# UART.net
KiCad netlist of a schematic drawn in Altium Designer
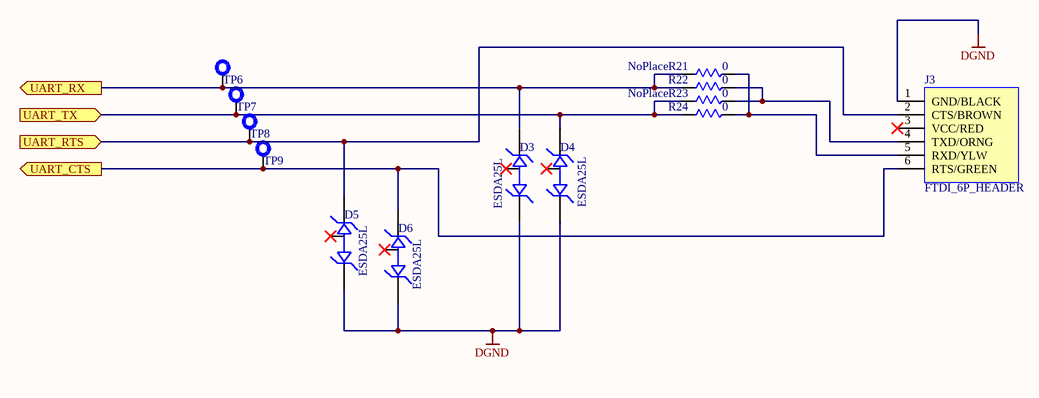
[diagram p0: UART.SchDoc]

(export (version "E")
  (design (tool "Eeschema 10.0.6"))
  (components
    (comp (ref "D3")
      (value "ESDA25L")
      (footprint "SOT23_3_HD")
      (description "TRANSIL ARRAY DUAL ESD SOT-23")
      (fields (field (name "MANUFACTURER") "STMicroelectronics"))
      (libsource (lib "ECGLib") (part "ESDA25L"))
    )
    (comp (ref "D4")
      (value "ESDA25L")
      (footprint "SOT23_3_HD")
      (description "TRANSIL ARRAY DUAL ESD SOT-23")
      (fields (field (name "MANUFACTURER") "STMicroelectronics"))
      (libsource (lib "ECGLib") (part "ESDA25L"))
    )
    (comp (ref "D5")
      (value "ESDA25L")
      (footprint "SOT23_3_HD")
      (description "TRANSIL ARRAY DUAL ESD SOT-23")
      (fields (field (name "MANUFACTURER") "STMicroelectronics"))
      (libsource (lib "ECGLib") (part "ESDA25L"))
    )
    (comp (ref "D6")
      (value "ESDA25L")
      (footprint "SOT23_3_HD")
      (description "TRANSIL ARRAY DUAL ESD SOT-23")
      (fields (field (name "MANUFACTURER") "STMicroelectronics"))
      (libsource (lib "ECGLib") (part "ESDA25L"))
    )
    (comp (ref "J3")
      (value "FTDI_6P_HEADER")
      (footprint "GEC36SBSN-M89")
      (description "6 PIN FTDI HEADER")
      (fields
        (field (name "MANUFACTURER") "Sullins Connector Solutions")
        (field (name "MANUFACTURER PART NUMBER") "GEC36SBSN-M89")
      )
      (libsource (lib "ECGLib") (part "FTDI_6P_HEADER"))
    )
    (comp (ref "R21")
      (value "0")
      (footprint "RES_0603")
      (description "RES 0.0 OHM 0.1W JUMPER 0603 SMD")
      (fields
        (field (name "MANUFACTURER") "Bourns Inc")
        (field (name "MANUFACTURER PART NUMBER") "CR0603-J/-000ELF")
        (field (name "NOPLACE?") "NoPlace")
      )
      (libsource (lib "ECGLib") (part "RES_GEN"))
    )
    (comp (ref "R22")
      (value "0")
      (footprint "RES_0603")
      (description "RES 0.0 OHM 0.1W JUMPER 0603 SMD")
      (fields
        (field (name "MANUFACTURER") "Bourns Inc")
        (field (name "MANUFACTURER PART NUMBER") "CR0603-J/-000ELF")
      )
      (libsource (lib "ECGLib") (part "RES_GEN"))
    )
    (comp (ref "R23")
      (value "0")
      (footprint "RES_0603")
      (description "RES 0.0 OHM 0.1W JUMPER 0603 SMD")
      (fields
        (field (name "MANUFACTURER") "Bourns Inc")
        (field (name "MANUFACTURER PART NUMBER") "CR0603-J/-000ELF")
        (field (name "NOPLACE?") "NoPlace")
      )
      (libsource (lib "ECGLib") (part "RES_GEN"))
    )
    (comp (ref "R24")
      (value "0")
      (footprint "RES_0603")
      (description "RES 0.0 OHM 0.1W JUMPER 0603 SMD")
      (fields
        (field (name "MANUFACTURER") "Bourns Inc")
        (field (name "MANUFACTURER PART NUMBER") "CR0603-J/-000ELF")
      )
      (libsource (lib "ECGLib") (part "RES_GEN"))
    )
    (comp (ref "TP6")
      (value "TEST_PT_40MIL")
      (footprint "TP_40MIL")
      (description "40MIL DIAM TEST POINT")
      (libsource (lib "ECGLib") (part "TEST_PT_40MIL"))
    )
    (comp (ref "TP7")
      (value "TEST_PT_40MIL")
      (footprint "TP_40MIL")
      (description "40MIL DIAM TEST POINT")
      (libsource (lib "ECGLib") (part "TEST_PT_40MIL"))
    )
    (comp (ref "TP8")
      (value "TEST_PT_40MIL")
      (footprint "TP_40MIL")
      (description "40MIL DIAM TEST POINT")
      (libsource (lib "ECGLib") (part "TEST_PT_40MIL"))
    )
    (comp (ref "TP9")
      (value "TEST_PT_40MIL")
      (footprint "TP_40MIL")
      (description "40MIL DIAM TEST POINT")
      (libsource (lib "ECGLib") (part "TEST_PT_40MIL"))
    )
  )
  (nets
    (net (code "1") (name "/UART_CTS") (class "Default")
      (node (ref "D6") (pin "2") (pinfunction "2_2") (pintype "passive"))
      (node (ref "J3") (pin "6") (pinfunction "RTS/GREEN_6") (pintype "passive"))
      (node (ref "TP9") (pin "1") (pinfunction "1_1") (pintype "passive"))
    )
    (net (code "2") (name "/UART_RTS") (class "Default")
      (node (ref "D5") (pin "2") (pinfunction "2_2") (pintype "passive"))
      (node (ref "J3") (pin "2") (pinfunction "CTS/BROWN_2") (pintype "passive"))
      (node (ref "TP8") (pin "1") (pinfunction "1_1") (pintype "passive"))
    )
    (net (code "3") (name "/UART_RX") (class "Default")
      (node (ref "D3") (pin "2") (pinfunction "2_2") (pintype "passive"))
      (node (ref "R21") (pin "1") (pintype "passive"))
      (node (ref "R22") (pin "1") (pintype "passive"))
      (node (ref "TP6") (pin "1") (pinfunction "1_1") (pintype "passive"))
    )
    (net (code "4") (name "/UART_TX") (class "Default")
      (node (ref "D4") (pin "2") (pinfunction "2_2") (pintype "passive"))
      (node (ref "R23") (pin "1") (pintype "passive"))
      (node (ref "R24") (pin "1") (pintype "passive"))
      (node (ref "TP7") (pin "1") (pinfunction "1_1") (pintype "passive"))
    )
    (net (code "5") (name "DGND") (class "Default")
      (node (ref "D3") (pin "1") (pinfunction "1_1") (pintype "passive"))
      (node (ref "D4") (pin "1") (pinfunction "1_1") (pintype "passive"))
      (node (ref "D5") (pin "1") (pinfunction "1_1") (pintype "passive"))
      (node (ref "D6") (pin "1") (pinfunction "1_1") (pintype "passive"))
      (node (ref "J3") (pin "1") (pinfunction "GND/BLACK_1") (pintype "passive"))
    )
    (net (code "6") (name "Net-(J3-RXD{slash}YLW)") (class "Default")
      (node (ref "J3") (pin "5") (pinfunction "RXD/YLW_5") (pintype "passive"))
      (node (ref "R21") (pin "2") (pintype "passive"))
      (node (ref "R24") (pin "2") (pintype "passive"))
    )
    (net (code "7") (name "Net-(J3-TXD{slash}ORNG)") (class "Default")
      (node (ref "J3") (pin "4") (pinfunction "TXD/ORNG_4") (pintype "passive"))
      (node (ref "R22") (pin "2") (pintype "passive"))
      (node (ref "R23") (pin "2") (pintype "passive"))
    )
    (net (code "8") (name "unconnected-(D3-NC-Pad3)") (class "Default")
      (node (ref "D3") (pin "3") (pinfunction "NC_3") (pintype "passive+no_connect"))
    )
    (net (code "9") (name "unconnected-(D4-NC-Pad3)") (class "Default")
      (node (ref "D4") (pin "3") (pinfunction "NC_3") (pintype "passive+no_connect"))
    )
    (net (code "10") (name "unconnected-(D5-NC-Pad3)") (class "Default")
      (node (ref "D5") (pin "3") (pinfunction "NC_3") (pintype "passive+no_connect"))
    )
    (net (code "11") (name "unconnected-(D6-NC-Pad3)") (class "Default")
      (node (ref "D6") (pin "3") (pinfunction "NC_3") (pintype "passive+no_connect"))
    )
    (net (code "12") (name "unconnected-(J3-VCC{slash}RED-Pad3)") (class "Default")
      (node (ref "J3") (pin "3") (pinfunction "VCC/RED_3") (pintype "passive+no_connect"))
    )
  )
)
